# SpringReverb.net
KiCad netlist of a schematic drawn in EAGLE
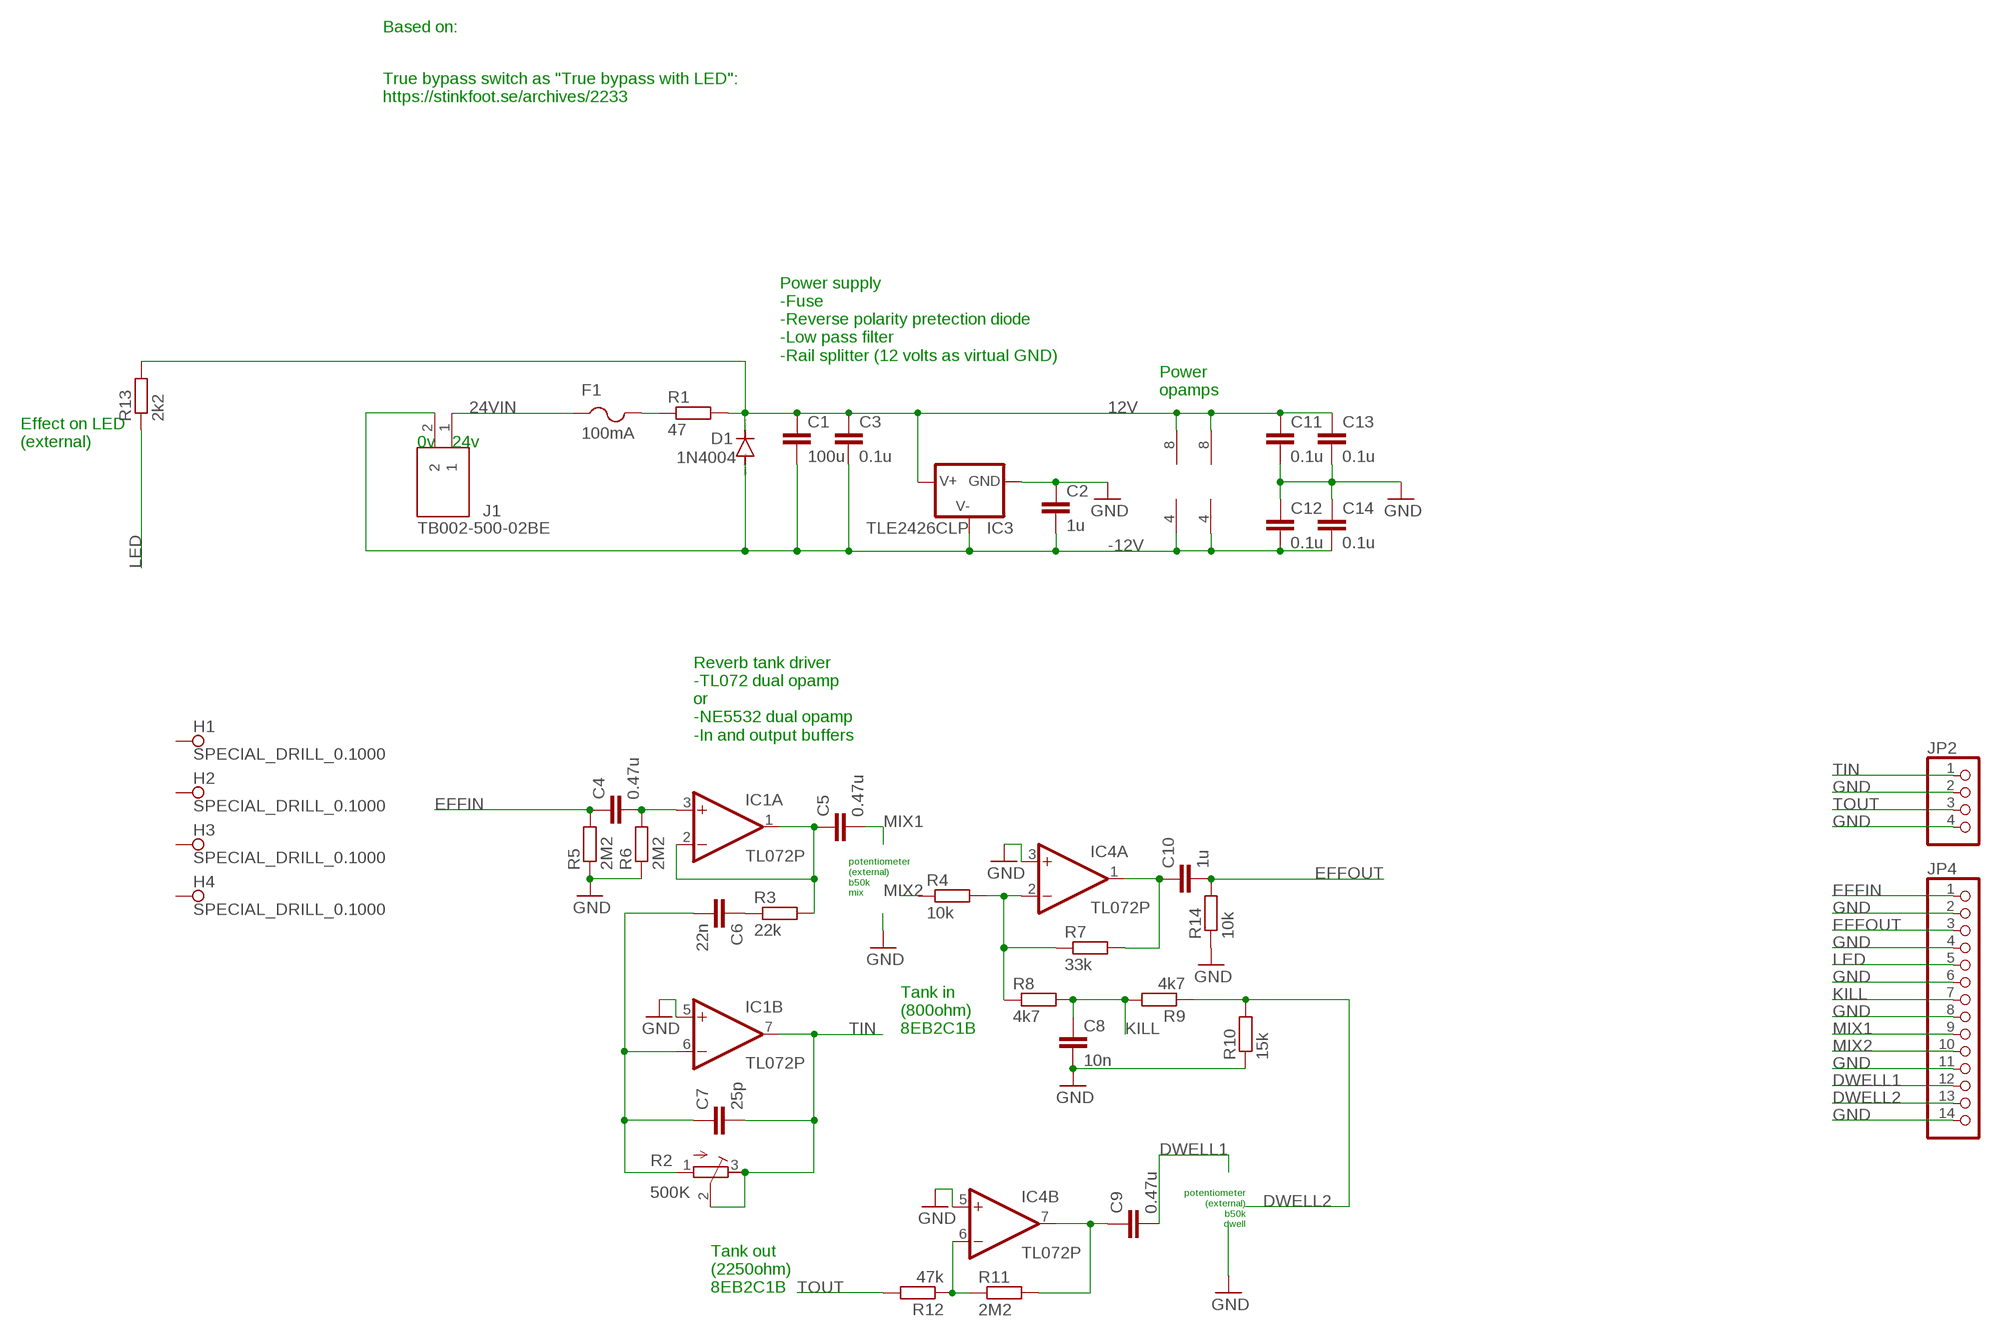
[diagram p0: schematic, sheet 1]

(export (version "E")
  (design (tool "Eeschema 10.0.6"))
  (components
    (comp (ref "C1")
      (value "100u")
      (footprint "eagle-import:C1206")
      (libsource (lib "eagle-import") (part "C-EUC1206"))
    )
    (comp (ref "C2")
      (value "1u")
      (footprint "eagle-import:C1206")
      (libsource (lib "eagle-import") (part "C-EUC1206"))
    )
    (comp (ref "C3")
      (value "0.1u")
      (footprint "eagle-import:C0603")
      (libsource (lib "eagle-import") (part "C-EUC0603"))
    )
    (comp (ref "C4")
      (value "0.47u")
      (footprint "eagle-import:C1206")
      (libsource (lib "eagle-import") (part "C-EUC1206"))
    )
    (comp (ref "C5")
      (value "0.47u")
      (footprint "eagle-import:C1206")
      (libsource (lib "eagle-import") (part "C-EUC1206"))
    )
    (comp (ref "C6")
      (value "22n")
      (footprint "eagle-import:C0603")
      (libsource (lib "eagle-import") (part "C-EUC0603"))
    )
    (comp (ref "C7")
      (value "25p")
      (footprint "eagle-import:C1206")
      (libsource (lib "eagle-import") (part "C-EUC1206"))
    )
    (comp (ref "C8")
      (value "10n")
      (footprint "eagle-import:C1206")
      (libsource (lib "eagle-import") (part "C-EUC1206"))
    )
    (comp (ref "C9")
      (value "0.47u")
      (footprint "eagle-import:C1206")
      (libsource (lib "eagle-import") (part "C-EUC1206"))
    )
    (comp (ref "C10")
      (value "1u")
      (footprint "eagle-import:C1206")
      (libsource (lib "eagle-import") (part "C-EUC1206"))
    )
    (comp (ref "C11")
      (value "0.1u")
      (footprint "eagle-import:C0603")
      (libsource (lib "eagle-import") (part "C-EUC0603"))
    )
    (comp (ref "C12")
      (value "0.1u")
      (footprint "eagle-import:C0603")
      (libsource (lib "eagle-import") (part "C-EUC0603"))
    )
    (comp (ref "C13")
      (value "0.1u")
      (footprint "eagle-import:C0603")
      (libsource (lib "eagle-import") (part "C-EUC0603"))
    )
    (comp (ref "C14")
      (value "0.1u")
      (footprint "eagle-import:C0603")
      (libsource (lib "eagle-import") (part "C-EUC0603"))
    )
    (comp (ref "D1")
      (value "1N4004")
      (footprint "eagle-import:DO41-10")
      (libsource (lib "eagle-import") (part "1N4004"))
    )
    (comp (ref "F1")
      (value "100mA")
      (footprint "eagle-import:1812")
      (libsource (lib "eagle-import") (part "PTCFUSE-1812"))
    )
    (comp (ref "H1")
      (value "SPECIAL_DRILL_0.1000")
      (footprint "eagle-import:PAD_0.1000")
      (libsource (lib "eagle-import") (part "SPECIAL_DRILL_0.1000"))
    )
    (comp (ref "H2")
      (value "SPECIAL_DRILL_0.1000")
      (footprint "eagle-import:PAD_0.1000")
      (libsource (lib "eagle-import") (part "SPECIAL_DRILL_0.1000"))
    )
    (comp (ref "H3")
      (value "SPECIAL_DRILL_0.1000")
      (footprint "eagle-import:PAD_0.1000")
      (libsource (lib "eagle-import") (part "SPECIAL_DRILL_0.1000"))
    )
    (comp (ref "H4")
      (value "SPECIAL_DRILL_0.1000")
      (footprint "eagle-import:PAD_0.1000")
      (libsource (lib "eagle-import") (part "SPECIAL_DRILL_0.1000"))
    )
    (comp (ref "IC1")
      (value "TL072P")
      (footprint "eagle-import:DIL08")
      (libsource (lib "eagle-import") (part "TL072P"))
    )
    (comp (ref "IC3")
      (value "TLE2426CLP")
      (footprint "eagle-import:TO92LP")
      (libsource (lib "eagle-import") (part "TLE2426CLP"))
    )
    (comp (ref "IC4")
      (value "TL072P")
      (footprint "eagle-import:DIL08")
      (libsource (lib "eagle-import") (part "TL072P"))
    )
    (comp (ref "J1")
      (value "TB002-500-02BE")
      (footprint "eagle-import:CUI_TB002-500-02BE")
      (fields (field (name "MANUFACTURER") "CUI"))
      (libsource (lib "eagle-import") (part "TB002-500-02BE"))
    )
    (comp (ref "JP2")
      (value "PINHD-1X4")
      (footprint "eagle-import:1X04")
      (libsource (lib "eagle-import") (part "PINHD-1X4"))
    )
    (comp (ref "JP4")
      (value "PINHD-1X14")
      (footprint "eagle-import:1X14")
      (libsource (lib "eagle-import") (part "PINHD-1X14"))
    )
    (comp (ref "R1")
      (value "47")
      (footprint "eagle-import:R0603")
      (libsource (lib "eagle-import") (part "R-EU_R0603"))
    )
    (comp (ref "R2")
      (value "500K")
      (footprint "eagle-import:RTRIM3296W")
      (libsource (lib "eagle-import") (part "R-TRIMM3296W"))
    )
    (comp (ref "R3")
      (value "22k")
      (footprint "eagle-import:R0603")
      (libsource (lib "eagle-import") (part "R-EU_R0603"))
    )
    (comp (ref "R4")
      (value "10k")
      (footprint "eagle-import:R0603")
      (libsource (lib "eagle-import") (part "R-EU_R0603"))
    )
    (comp (ref "R5")
      (value "2M2")
      (footprint "eagle-import:R1206")
      (libsource (lib "eagle-import") (part "R-EU_R1206"))
    )
    (comp (ref "R6")
      (value "2M2")
      (footprint "eagle-import:R1206")
      (libsource (lib "eagle-import") (part "R-EU_R1206"))
    )
    (comp (ref "R7")
      (value "33k")
      (footprint "eagle-import:R0603")
      (libsource (lib "eagle-import") (part "R-EU_R0603"))
    )
    (comp (ref "R8")
      (value "4k7")
      (footprint "eagle-import:R0603")
      (libsource (lib "eagle-import") (part "R-EU_R0603"))
    )
    (comp (ref "R9")
      (value "4k7")
      (footprint "eagle-import:R0603")
      (libsource (lib "eagle-import") (part "R-EU_R0603"))
    )
    (comp (ref "R10")
      (value "15k")
      (footprint "eagle-import:R1206")
      (libsource (lib "eagle-import") (part "R-EU_R1206"))
    )
    (comp (ref "R11")
      (value "2M2")
      (footprint "eagle-import:R1206")
      (libsource (lib "eagle-import") (part "R-EU_R1206"))
    )
    (comp (ref "R12")
      (value "47k")
      (footprint "eagle-import:R0603")
      (libsource (lib "eagle-import") (part "R-EU_R0603"))
    )
    (comp (ref "R13")
      (value "2k2")
      (footprint "eagle-import:R0603")
      (libsource (lib "eagle-import") (part "R-EU_R0603"))
    )
    (comp (ref "R14")
      (value "10k")
      (footprint "eagle-import:R0603")
      (libsource (lib "eagle-import") (part "R-EU_R0603"))
    )
  )
  (nets
    (net (code "1") (name "/-12V") (class "Default")
      (node (ref "C1") (pin "2") (pinfunction "2_2") (pintype "passive"))
      (node (ref "C12") (pin "2") (pinfunction "2_2") (pintype "passive"))
      (node (ref "C14") (pin "2") (pinfunction "2_2") (pintype "passive"))
      (node (ref "C2") (pin "2") (pinfunction "2_2") (pintype "passive"))
      (node (ref "C3") (pin "2") (pinfunction "2_2") (pintype "passive"))
      (node (ref "D1") (pin "A") (pinfunction "A_A") (pintype "passive"))
      (node (ref "IC1") (pin "4") (pinfunction "V-_4") (pintype "power_in"))
      (node (ref "IC3") (pin "GND") (pinfunction "GND_GND") (pintype "input"))
      (node (ref "IC4") (pin "4") (pinfunction "V-_4") (pintype "power_in"))
      (node (ref "J1") (pin "2") (pinfunction "2_2") (pintype "passive"))
    )
    (net (code "2") (name "/12V") (class "Default")
      (node (ref "C1") (pin "1") (pinfunction "1_1") (pintype "passive"))
      (node (ref "C11") (pin "1") (pinfunction "1_1") (pintype "passive"))
      (node (ref "C13") (pin "1") (pinfunction "1_1") (pintype "passive"))
      (node (ref "C3") (pin "1") (pinfunction "1_1") (pintype "passive"))
      (node (ref "D1") (pin "C") (pinfunction "C_C") (pintype "passive"))
      (node (ref "IC1") (pin "8") (pinfunction "V+_8") (pintype "power_in"))
      (node (ref "IC3") (pin "IN") (pinfunction "IN_IN") (pintype "input"))
      (node (ref "IC4") (pin "8") (pinfunction "V+_8") (pintype "power_in"))
      (node (ref "R1") (pin "2") (pinfunction "2_2") (pintype "passive"))
      (node (ref "R13") (pin "2") (pinfunction "2_2") (pintype "passive"))
    )
    (net (code "3") (name "/24VIN") (class "Default")
      (node (ref "F1") (pin "1") (pinfunction "1_1") (pintype "passive"))
      (node (ref "J1") (pin "1") (pinfunction "1_1") (pintype "passive"))
    )
    (net (code "4") (name "/DWELL1") (class "Default")
      (node (ref "C9") (pin "2") (pinfunction "2_2") (pintype "passive"))
      (node (ref "JP4") (pin "12") (pinfunction "12_12") (pintype "passive"))
    )
    (net (code "5") (name "/DWELL2") (class "Default")
      (node (ref "JP4") (pin "13") (pinfunction "13_13") (pintype "passive"))
      (node (ref "R10") (pin "2") (pinfunction "2_2") (pintype "passive"))
      (node (ref "R9") (pin "1") (pinfunction "1_1") (pintype "passive"))
    )
    (net (code "6") (name "/EFFIN") (class "Default")
      (node (ref "C4") (pin "1") (pinfunction "1_1") (pintype "passive"))
      (node (ref "JP4") (pin "1") (pinfunction "1_1") (pintype "passive"))
      (node (ref "R5") (pin "2") (pinfunction "2_2") (pintype "passive"))
    )
    (net (code "7") (name "/EFFOUT") (class "Default")
      (node (ref "C10") (pin "2") (pinfunction "2_2") (pintype "passive"))
      (node (ref "JP4") (pin "3") (pinfunction "3_3") (pintype "passive"))
      (node (ref "R14") (pin "2") (pinfunction "2_2") (pintype "passive"))
    )
    (net (code "8") (name "/KILL") (class "Default")
      (node (ref "C8") (pin "1") (pinfunction "1_1") (pintype "passive"))
      (node (ref "JP4") (pin "7") (pinfunction "7_7") (pintype "passive"))
      (node (ref "R8") (pin "2") (pinfunction "2_2") (pintype "passive"))
      (node (ref "R9") (pin "2") (pinfunction "2_2") (pintype "passive"))
    )
    (net (code "9") (name "/LED") (class "Default")
      (node (ref "JP4") (pin "5") (pinfunction "5_5") (pintype "passive"))
      (node (ref "R13") (pin "1") (pinfunction "1_1") (pintype "passive"))
    )
    (net (code "10") (name "/MIX1") (class "Default")
      (node (ref "C5") (pin "2") (pinfunction "2_2") (pintype "passive"))
      (node (ref "JP4") (pin "9") (pinfunction "9_9") (pintype "passive"))
    )
    (net (code "11") (name "/MIX2") (class "Default")
      (node (ref "JP4") (pin "10") (pinfunction "10_10") (pintype "passive"))
      (node (ref "R4") (pin "1") (pinfunction "1_1") (pintype "passive"))
    )
    (net (code "12") (name "/TIN") (class "Default")
      (node (ref "C7") (pin "2") (pinfunction "2_2") (pintype "passive"))
      (node (ref "IC1") (pin "7") (pinfunction "OUT_7") (pintype "output"))
      (node (ref "JP2") (pin "1") (pinfunction "1_1") (pintype "passive"))
      (node (ref "R2") (pin "2") (pinfunction "S_2") (pintype "passive"))
      (node (ref "R2") (pin "3") (pinfunction "E_3") (pintype "passive"))
    )
    (net (code "13") (name "/TOUT") (class "Default")
      (node (ref "JP2") (pin "3") (pinfunction "3_3") (pintype "passive"))
      (node (ref "R12") (pin "2") (pinfunction "2_2") (pintype "passive"))
    )
    (net (code "14") (name "GND") (class "Default")
      (node (ref "C11") (pin "2") (pinfunction "2_2") (pintype "passive"))
      (node (ref "C12") (pin "1") (pinfunction "1_1") (pintype "passive"))
      (node (ref "C13") (pin "2") (pinfunction "2_2") (pintype "passive"))
      (node (ref "C14") (pin "1") (pinfunction "1_1") (pintype "passive"))
      (node (ref "C2") (pin "1") (pinfunction "1_1") (pintype "passive"))
      (node (ref "C8") (pin "2") (pinfunction "2_2") (pintype "passive"))
      (node (ref "IC1") (pin "5") (pinfunction "+IN_5") (pintype "input"))
      (node (ref "IC3") (pin "OUT") (pinfunction "OUT_OUT") (pintype "passive"))
      (node (ref "IC4") (pin "3") (pinfunction "+IN_3") (pintype "input"))
      (node (ref "IC4") (pin "5") (pinfunction "+IN_5") (pintype "input"))
      (node (ref "JP2") (pin "2") (pinfunction "2_2") (pintype "passive"))
      (node (ref "JP2") (pin "4") (pinfunction "4_4") (pintype "passive"))
      (node (ref "JP4") (pin "11") (pinfunction "11_11") (pintype "passive"))
      (node (ref "JP4") (pin "14") (pinfunction "14_14") (pintype "passive"))
      (node (ref "JP4") (pin "2") (pinfunction "2_2") (pintype "passive"))
      (node (ref "JP4") (pin "4") (pinfunction "4_4") (pintype "passive"))
      (node (ref "JP4") (pin "6") (pinfunction "6_6") (pintype "passive"))
      (node (ref "JP4") (pin "8") (pinfunction "8_8") (pintype "passive"))
      (node (ref "R10") (pin "1") (pinfunction "1_1") (pintype "passive"))
      (node (ref "R14") (pin "1") (pinfunction "1_1") (pintype "passive"))
      (node (ref "R5") (pin "1") (pinfunction "1_1") (pintype "passive"))
      (node (ref "R6") (pin "1") (pinfunction "1_1") (pintype "passive"))
    )
    (net (code "15") (name "Net-(C6-Pad1)") (class "Default")
      (node (ref "C6") (pin "1") (pinfunction "1_1") (pintype "passive"))
      (node (ref "R3") (pin "1") (pinfunction "1_1") (pintype "passive"))
    )
    (net (code "16") (name "Net-(F1-Pad2)") (class "Default")
      (node (ref "F1") (pin "2") (pinfunction "2_2") (pintype "passive"))
      (node (ref "R1") (pin "1") (pinfunction "1_1") (pintype "passive"))
    )
    (net (code "17") (name "Net-(IC1A-+IN)") (class "Default")
      (node (ref "C4") (pin "2") (pinfunction "2_2") (pintype "passive"))
      (node (ref "IC1") (pin "3") (pinfunction "+IN_3") (pintype "input"))
      (node (ref "R6") (pin "2") (pinfunction "2_2") (pintype "passive"))
    )
    (net (code "18") (name "Net-(IC1A--IN)") (class "Default")
      (node (ref "C5") (pin "1") (pinfunction "1_1") (pintype "passive"))
      (node (ref "IC1") (pin "1") (pinfunction "OUT_1") (pintype "output"))
      (node (ref "IC1") (pin "2") (pinfunction "-IN_2") (pintype "input"))
      (node (ref "R3") (pin "2") (pinfunction "2_2") (pintype "passive"))
    )
    (net (code "19") (name "Net-(IC1B--IN)") (class "Default")
      (node (ref "C6") (pin "2") (pinfunction "2_2") (pintype "passive"))
      (node (ref "C7") (pin "1") (pinfunction "1_1") (pintype "passive"))
      (node (ref "IC1") (pin "6") (pinfunction "-IN_6") (pintype "input"))
      (node (ref "R2") (pin "1") (pinfunction "A_1") (pintype "passive"))
    )
    (net (code "20") (name "Net-(IC4A--IN)") (class "Default")
      (node (ref "IC4") (pin "2") (pinfunction "-IN_2") (pintype "input"))
      (node (ref "R4") (pin "2") (pinfunction "2_2") (pintype "passive"))
      (node (ref "R7") (pin "1") (pinfunction "1_1") (pintype "passive"))
      (node (ref "R8") (pin "1") (pinfunction "1_1") (pintype "passive"))
    )
    (net (code "21") (name "Net-(IC4A-OUT)") (class "Default")
      (node (ref "C10") (pin "1") (pinfunction "1_1") (pintype "passive"))
      (node (ref "IC4") (pin "1") (pinfunction "OUT_1") (pintype "output"))
      (node (ref "R7") (pin "2") (pinfunction "2_2") (pintype "passive"))
    )
    (net (code "22") (name "Net-(IC4B--IN)") (class "Default")
      (node (ref "IC4") (pin "6") (pinfunction "-IN_6") (pintype "input"))
      (node (ref "R11") (pin "1") (pinfunction "1_1") (pintype "passive"))
      (node (ref "R12") (pin "1") (pinfunction "1_1") (pintype "passive"))
    )
    (net (code "23") (name "Net-(IC4B-OUT)") (class "Default")
      (node (ref "C9") (pin "1") (pinfunction "1_1") (pintype "passive"))
      (node (ref "IC4") (pin "7") (pinfunction "OUT_7") (pintype "output"))
      (node (ref "R11") (pin "2") (pinfunction "2_2") (pintype "passive"))
    )
    (net (code "24") (name "unconnected-(H1-Pad1)") (class "Default")
      (node (ref "H1") (pin "1") (pinfunction "1_1") (pintype "passive"))
    )
    (net (code "25") (name "unconnected-(H2-Pad1)") (class "Default")
      (node (ref "H2") (pin "1") (pinfunction "1_1") (pintype "passive"))
    )
    (net (code "26") (name "unconnected-(H3-Pad1)") (class "Default")
      (node (ref "H3") (pin "1") (pinfunction "1_1") (pintype "passive"))
    )
    (net (code "27") (name "unconnected-(H4-Pad1)") (class "Default")
      (node (ref "H4") (pin "1") (pinfunction "1_1") (pintype "passive"))
    )
  )
)
